# shieldrasp2.net
KiCad netlist of a schematic drawn in EAGLE
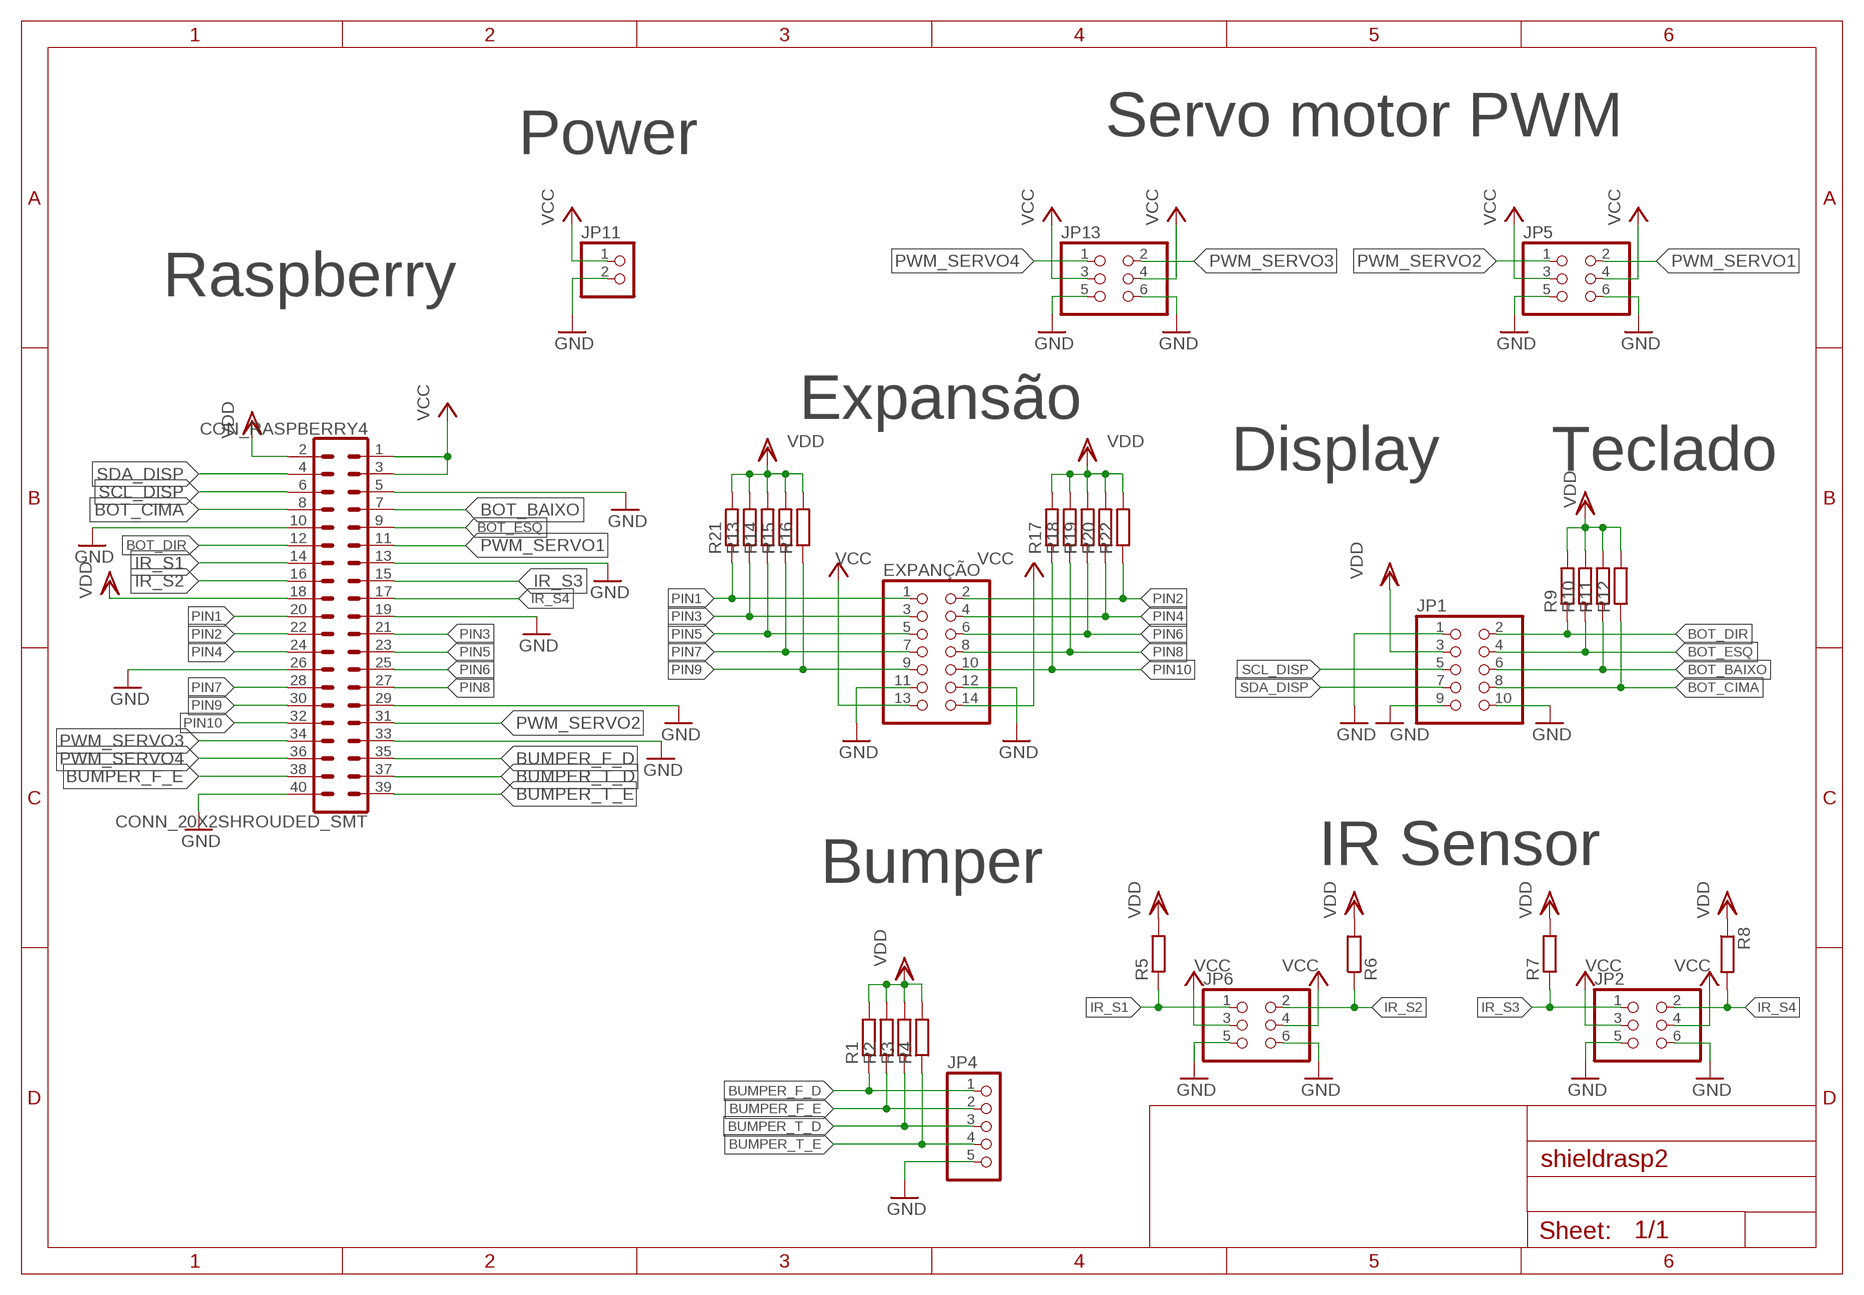
[diagram p0: schematic, sheet 1]

(export (version "E")
  (design (tool "Eeschema 10.0.6"))
  (components
    (comp (ref "CON_RASPBERRY4")
      (value "CONN_20X2SHROUDED_SMT")
      (footprint "eagle-import:2X20_SHROUDED_SMT")
      (libsource (lib "eagle-import") (part "CONN_20X2SHROUDED_SMT"))
    )
    (comp (ref "EXPANÇÃO")
      (value "PINHD-2X7")
      (footprint "eagle-import:2X07")
      (libsource (lib "eagle-import") (part "PINHD-2X7"))
    )
    (comp (ref "JP1")
      (value "PINHD-2X5/90")
      (footprint "eagle-import:2X05_90")
      (libsource (lib "eagle-import") (part "PINHD-2X5/90"))
    )
    (comp (ref "JP2")
      (value "PINHD-2X3/90")
      (footprint "eagle-import:2X03_90")
      (libsource (lib "eagle-import") (part "PINHD-2X3/90"))
    )
    (comp (ref "JP4")
      (value "PINHD-1X5/90")
      (footprint "eagle-import:1X05_90")
      (libsource (lib "eagle-import") (part "PINHD-1X5/90"))
    )
    (comp (ref "JP5")
      (value "PINHD-2X3/90")
      (footprint "eagle-import:2X03_90")
      (libsource (lib "eagle-import") (part "PINHD-2X3/90"))
    )
    (comp (ref "JP6")
      (value "PINHD-2X3/90")
      (footprint "eagle-import:2X03_90")
      (libsource (lib "eagle-import") (part "PINHD-2X3/90"))
    )
    (comp (ref "JP11")
      (value "PINHD-1X2/90")
      (footprint "eagle-import:1X02_90")
      (libsource (lib "eagle-import") (part "PINHD-1X2/90"))
    )
    (comp (ref "JP13")
      (value "PINHD-2X3/90")
      (footprint "eagle-import:2X03_90")
      (libsource (lib "eagle-import") (part "PINHD-2X3/90"))
    )
    (comp (ref "R1")
      (value "R-EU_M0805")
      (footprint "eagle-import:M0805")
      (libsource (lib "eagle-import") (part "R-EU_M0805"))
    )
    (comp (ref "R2")
      (value "R-EU_M0805")
      (footprint "eagle-import:M0805")
      (libsource (lib "eagle-import") (part "R-EU_M0805"))
    )
    (comp (ref "R3")
      (value "R-EU_M0805")
      (footprint "eagle-import:M0805")
      (libsource (lib "eagle-import") (part "R-EU_M0805"))
    )
    (comp (ref "R4")
      (value "R-EU_M0805")
      (footprint "eagle-import:M0805")
      (libsource (lib "eagle-import") (part "R-EU_M0805"))
    )
    (comp (ref "R5")
      (value "R-EU_M0805")
      (footprint "eagle-import:M0805")
      (libsource (lib "eagle-import") (part "R-EU_M0805"))
    )
    (comp (ref "R6")
      (value "R-EU_M0805")
      (footprint "eagle-import:M0805")
      (libsource (lib "eagle-import") (part "R-EU_M0805"))
    )
    (comp (ref "R7")
      (value "R-EU_M0805")
      (footprint "eagle-import:M0805")
      (libsource (lib "eagle-import") (part "R-EU_M0805"))
    )
    (comp (ref "R8")
      (value "R-EU_M0805")
      (footprint "eagle-import:M0805")
      (libsource (lib "eagle-import") (part "R-EU_M0805"))
    )
    (comp (ref "R9")
      (value "R-EU_M0805")
      (footprint "eagle-import:M0805")
      (libsource (lib "eagle-import") (part "R-EU_M0805"))
    )
    (comp (ref "R10")
      (value "R-EU_M0805")
      (footprint "eagle-import:M0805")
      (libsource (lib "eagle-import") (part "R-EU_M0805"))
    )
    (comp (ref "R11")
      (value "R-EU_M0805")
      (footprint "eagle-import:M0805")
      (libsource (lib "eagle-import") (part "R-EU_M0805"))
    )
    (comp (ref "R12")
      (value "R-EU_M0805")
      (footprint "eagle-import:M0805")
      (libsource (lib "eagle-import") (part "R-EU_M0805"))
    )
    (comp (ref "R13")
      (value "R-EU_M0805")
      (footprint "eagle-import:M0805")
      (libsource (lib "eagle-import") (part "R-EU_M0805"))
    )
    (comp (ref "R14")
      (value "R-EU_M0805")
      (footprint "eagle-import:M0805")
      (libsource (lib "eagle-import") (part "R-EU_M0805"))
    )
    (comp (ref "R15")
      (value "R-EU_M0805")
      (footprint "eagle-import:M0805")
      (libsource (lib "eagle-import") (part "R-EU_M0805"))
    )
    (comp (ref "R16")
      (value "R-EU_M0805")
      (footprint "eagle-import:M0805")
      (libsource (lib "eagle-import") (part "R-EU_M0805"))
    )
    (comp (ref "R17")
      (value "R-EU_M0805")
      (footprint "eagle-import:M0805")
      (libsource (lib "eagle-import") (part "R-EU_M0805"))
    )
    (comp (ref "R18")
      (value "R-EU_M0805")
      (footprint "eagle-import:M0805")
      (libsource (lib "eagle-import") (part "R-EU_M0805"))
    )
    (comp (ref "R19")
      (value "R-EU_M0805")
      (footprint "eagle-import:M0805")
      (libsource (lib "eagle-import") (part "R-EU_M0805"))
    )
    (comp (ref "R20")
      (value "R-EU_M0805")
      (footprint "eagle-import:M0805")
      (libsource (lib "eagle-import") (part "R-EU_M0805"))
    )
    (comp (ref "R21")
      (value "R-EU_M0805")
      (footprint "eagle-import:M0805")
      (libsource (lib "eagle-import") (part "R-EU_M0805"))
    )
    (comp (ref "R22")
      (value "R-EU_M0805")
      (footprint "eagle-import:M0805")
      (libsource (lib "eagle-import") (part "R-EU_M0805"))
    )
  )
  (nets
    (net (code "1") (name "BOT_BAIXO") (class "Default")
      (node (ref "CON_RASPBERRY4") (pin "7") (pinfunction "7_7") (pintype "passive"))
      (node (ref "JP1") (pin "6") (pinfunction "6_6") (pintype "passive"))
      (node (ref "R11") (pin "1") (pinfunction "1_1") (pintype "passive"))
    )
    (net (code "2") (name "BOT_CIMA") (class "Default")
      (node (ref "CON_RASPBERRY4") (pin "8") (pinfunction "8_8") (pintype "passive"))
      (node (ref "JP1") (pin "8") (pinfunction "8_8") (pintype "passive"))
      (node (ref "R12") (pin "1") (pinfunction "1_1") (pintype "passive"))
    )
    (net (code "3") (name "BOT_DIR") (class "Default")
      (node (ref "CON_RASPBERRY4") (pin "12") (pinfunction "12_12") (pintype "passive"))
      (node (ref "JP1") (pin "2") (pinfunction "2_2") (pintype "passive"))
      (node (ref "R9") (pin "1") (pinfunction "1_1") (pintype "passive"))
    )
    (net (code "4") (name "BOT_ESQ") (class "Default")
      (node (ref "CON_RASPBERRY4") (pin "9") (pinfunction "9_9") (pintype "passive"))
      (node (ref "JP1") (pin "4") (pinfunction "4_4") (pintype "passive"))
      (node (ref "R10") (pin "1") (pinfunction "1_1") (pintype "passive"))
    )
    (net (code "5") (name "BUMPER_F_D") (class "Default")
      (node (ref "CON_RASPBERRY4") (pin "35") (pinfunction "35_35") (pintype "passive"))
      (node (ref "JP4") (pin "1") (pinfunction "1_1") (pintype "passive"))
      (node (ref "R1") (pin "1") (pinfunction "1_1") (pintype "passive"))
    )
    (net (code "6") (name "BUMPER_F_E") (class "Default")
      (node (ref "CON_RASPBERRY4") (pin "38") (pinfunction "38_38") (pintype "passive"))
      (node (ref "JP4") (pin "2") (pinfunction "2_2") (pintype "passive"))
      (node (ref "R2") (pin "1") (pinfunction "1_1") (pintype "passive"))
    )
    (net (code "7") (name "BUMPER_T_D") (class "Default")
      (node (ref "CON_RASPBERRY4") (pin "37") (pinfunction "37_37") (pintype "passive"))
      (node (ref "JP4") (pin "3") (pinfunction "3_3") (pintype "passive"))
      (node (ref "R3") (pin "1") (pinfunction "1_1") (pintype "passive"))
    )
    (net (code "8") (name "BUMPER_T_E") (class "Default")
      (node (ref "CON_RASPBERRY4") (pin "39") (pinfunction "39_39") (pintype "passive"))
      (node (ref "JP4") (pin "4") (pinfunction "4_4") (pintype "passive"))
      (node (ref "R4") (pin "1") (pinfunction "1_1") (pintype "passive"))
    )
    (net (code "9") (name "GND") (class "Default")
      (node (ref "CON_RASPBERRY4") (pin "10") (pinfunction "10_10") (pintype "passive"))
      (node (ref "CON_RASPBERRY4") (pin "13") (pinfunction "13_13") (pintype "passive"))
      (node (ref "CON_RASPBERRY4") (pin "19") (pinfunction "19_19") (pintype "passive"))
      (node (ref "CON_RASPBERRY4") (pin "26") (pinfunction "26_26") (pintype "passive"))
      (node (ref "CON_RASPBERRY4") (pin "29") (pinfunction "29_29") (pintype "passive"))
      (node (ref "CON_RASPBERRY4") (pin "33") (pinfunction "33_33") (pintype "passive"))
      (node (ref "CON_RASPBERRY4") (pin "40") (pinfunction "40_40") (pintype "passive"))
      (node (ref "CON_RASPBERRY4") (pin "5") (pinfunction "5_5") (pintype "passive"))
      (node (ref "EXPANÇÃO") (pin "11") (pinfunction "11_11") (pintype "passive"))
      (node (ref "EXPANÇÃO") (pin "12") (pinfunction "12_12") (pintype "passive"))
      (node (ref "JP1") (pin "1") (pinfunction "1_1") (pintype "passive"))
      (node (ref "JP1") (pin "10") (pinfunction "10_10") (pintype "passive"))
      (node (ref "JP1") (pin "9") (pinfunction "9_9") (pintype "passive"))
      (node (ref "JP11") (pin "2") (pinfunction "2_2") (pintype "passive"))
      (node (ref "JP13") (pin "5") (pinfunction "5_5") (pintype "passive"))
      (node (ref "JP13") (pin "6") (pinfunction "6_6") (pintype "passive"))
      (node (ref "JP2") (pin "5") (pinfunction "5_5") (pintype "passive"))
      (node (ref "JP2") (pin "6") (pinfunction "6_6") (pintype "passive"))
      (node (ref "JP4") (pin "5") (pinfunction "5_5") (pintype "passive"))
      (node (ref "JP5") (pin "5") (pinfunction "5_5") (pintype "passive"))
      (node (ref "JP5") (pin "6") (pinfunction "6_6") (pintype "passive"))
      (node (ref "JP6") (pin "5") (pinfunction "5_5") (pintype "passive"))
      (node (ref "JP6") (pin "6") (pinfunction "6_6") (pintype "passive"))
    )
    (net (code "10") (name "IR_S1") (class "Default")
      (node (ref "CON_RASPBERRY4") (pin "14") (pinfunction "14_14") (pintype "passive"))
      (node (ref "JP6") (pin "1") (pinfunction "1_1") (pintype "passive"))
      (node (ref "R5") (pin "1") (pinfunction "1_1") (pintype "passive"))
    )
    (net (code "11") (name "IR_S2") (class "Default")
      (node (ref "CON_RASPBERRY4") (pin "16") (pinfunction "16_16") (pintype "passive"))
      (node (ref "JP6") (pin "2") (pinfunction "2_2") (pintype "passive"))
      (node (ref "R6") (pin "1") (pinfunction "1_1") (pintype "passive"))
    )
    (net (code "12") (name "IR_S3") (class "Default")
      (node (ref "CON_RASPBERRY4") (pin "15") (pinfunction "15_15") (pintype "passive"))
      (node (ref "JP2") (pin "1") (pinfunction "1_1") (pintype "passive"))
      (node (ref "R7") (pin "1") (pinfunction "1_1") (pintype "passive"))
    )
    (net (code "13") (name "IR_S4") (class "Default")
      (node (ref "CON_RASPBERRY4") (pin "17") (pinfunction "17_17") (pintype "passive"))
      (node (ref "JP2") (pin "2") (pinfunction "2_2") (pintype "passive"))
      (node (ref "R8") (pin "2") (pinfunction "2_2") (pintype "passive"))
    )
    (net (code "14") (name "PIN1") (class "Default")
      (node (ref "CON_RASPBERRY4") (pin "20") (pinfunction "20_20") (pintype "passive"))
      (node (ref "EXPANÇÃO") (pin "1") (pinfunction "1_1") (pintype "passive"))
      (node (ref "R21") (pin "1") (pinfunction "1_1") (pintype "passive"))
    )
    (net (code "15") (name "PIN2") (class "Default")
      (node (ref "CON_RASPBERRY4") (pin "22") (pinfunction "22_22") (pintype "passive"))
      (node (ref "EXPANÇÃO") (pin "2") (pinfunction "2_2") (pintype "passive"))
      (node (ref "R22") (pin "1") (pinfunction "1_1") (pintype "passive"))
    )
    (net (code "16") (name "PIN3") (class "Default")
      (node (ref "CON_RASPBERRY4") (pin "21") (pinfunction "21_21") (pintype "passive"))
      (node (ref "EXPANÇÃO") (pin "3") (pinfunction "3_3") (pintype "passive"))
      (node (ref "R13") (pin "1") (pinfunction "1_1") (pintype "passive"))
    )
    (net (code "17") (name "PIN4") (class "Default")
      (node (ref "CON_RASPBERRY4") (pin "24") (pinfunction "24_24") (pintype "passive"))
      (node (ref "EXPANÇÃO") (pin "4") (pinfunction "4_4") (pintype "passive"))
      (node (ref "R20") (pin "1") (pinfunction "1_1") (pintype "passive"))
    )
    (net (code "18") (name "PIN5") (class "Default")
      (node (ref "CON_RASPBERRY4") (pin "23") (pinfunction "23_23") (pintype "passive"))
      (node (ref "EXPANÇÃO") (pin "5") (pinfunction "5_5") (pintype "passive"))
      (node (ref "R14") (pin "1") (pinfunction "1_1") (pintype "passive"))
    )
    (net (code "19") (name "PIN6") (class "Default")
      (node (ref "CON_RASPBERRY4") (pin "25") (pinfunction "25_25") (pintype "passive"))
      (node (ref "EXPANÇÃO") (pin "6") (pinfunction "6_6") (pintype "passive"))
      (node (ref "R19") (pin "1") (pinfunction "1_1") (pintype "passive"))
    )
    (net (code "20") (name "PIN7") (class "Default")
      (node (ref "CON_RASPBERRY4") (pin "28") (pinfunction "28_28") (pintype "passive"))
      (node (ref "EXPANÇÃO") (pin "7") (pinfunction "7_7") (pintype "passive"))
      (node (ref "R15") (pin "1") (pinfunction "1_1") (pintype "passive"))
    )
    (net (code "21") (name "PIN8") (class "Default")
      (node (ref "CON_RASPBERRY4") (pin "27") (pinfunction "27_27") (pintype "passive"))
      (node (ref "EXPANÇÃO") (pin "8") (pinfunction "8_8") (pintype "passive"))
      (node (ref "R18") (pin "1") (pinfunction "1_1") (pintype "passive"))
    )
    (net (code "22") (name "PIN9") (class "Default")
      (node (ref "CON_RASPBERRY4") (pin "30") (pinfunction "30_30") (pintype "passive"))
      (node (ref "EXPANÇÃO") (pin "9") (pinfunction "9_9") (pintype "passive"))
      (node (ref "R16") (pin "1") (pinfunction "1_1") (pintype "passive"))
    )
    (net (code "23") (name "PIN10") (class "Default")
      (node (ref "CON_RASPBERRY4") (pin "32") (pinfunction "32_32") (pintype "passive"))
      (node (ref "EXPANÇÃO") (pin "10") (pinfunction "10_10") (pintype "passive"))
      (node (ref "R17") (pin "1") (pinfunction "1_1") (pintype "passive"))
    )
    (net (code "24") (name "PWM_SERVO1") (class "Default")
      (node (ref "CON_RASPBERRY4") (pin "11") (pinfunction "11_11") (pintype "passive"))
      (node (ref "JP5") (pin "2") (pinfunction "2_2") (pintype "passive"))
    )
    (net (code "25") (name "PWM_SERVO2") (class "Default")
      (node (ref "CON_RASPBERRY4") (pin "31") (pinfunction "31_31") (pintype "passive"))
      (node (ref "JP5") (pin "1") (pinfunction "1_1") (pintype "passive"))
    )
    (net (code "26") (name "PWM_SERVO3") (class "Default")
      (node (ref "CON_RASPBERRY4") (pin "34") (pinfunction "34_34") (pintype "passive"))
      (node (ref "JP13") (pin "2") (pinfunction "2_2") (pintype "passive"))
    )
    (net (code "27") (name "PWM_SERVO4") (class "Default")
      (node (ref "CON_RASPBERRY4") (pin "36") (pinfunction "36_36") (pintype "passive"))
      (node (ref "JP13") (pin "1") (pinfunction "1_1") (pintype "passive"))
    )
    (net (code "28") (name "SCL_DISP") (class "Default")
      (node (ref "CON_RASPBERRY4") (pin "6") (pinfunction "6_6") (pintype "passive"))
      (node (ref "JP1") (pin "5") (pinfunction "5_5") (pintype "passive"))
    )
    (net (code "29") (name "SDA_DISP") (class "Default")
      (node (ref "CON_RASPBERRY4") (pin "4") (pinfunction "4_4") (pintype "passive"))
      (node (ref "JP1") (pin "7") (pinfunction "7_7") (pintype "passive"))
    )
    (net (code "30") (name "VCC") (class "Default")
      (node (ref "CON_RASPBERRY4") (pin "1") (pinfunction "1_1") (pintype "passive"))
      (node (ref "CON_RASPBERRY4") (pin "3") (pinfunction "3_3") (pintype "passive"))
      (node (ref "EXPANÇÃO") (pin "13") (pinfunction "13_13") (pintype "passive"))
      (node (ref "EXPANÇÃO") (pin "14") (pinfunction "14_14") (pintype "passive"))
      (node (ref "JP11") (pin "1") (pinfunction "1_1") (pintype "passive"))
      (node (ref "JP13") (pin "3") (pinfunction "3_3") (pintype "passive"))
      (node (ref "JP13") (pin "4") (pinfunction "4_4") (pintype "passive"))
      (node (ref "JP2") (pin "3") (pinfunction "3_3") (pintype "passive"))
      (node (ref "JP2") (pin "4") (pinfunction "4_4") (pintype "passive"))
      (node (ref "JP5") (pin "3") (pinfunction "3_3") (pintype "passive"))
      (node (ref "JP5") (pin "4") (pinfunction "4_4") (pintype "passive"))
      (node (ref "JP6") (pin "3") (pinfunction "3_3") (pintype "passive"))
      (node (ref "JP6") (pin "4") (pinfunction "4_4") (pintype "passive"))
    )
    (net (code "31") (name "VDD") (class "Default")
      (node (ref "CON_RASPBERRY4") (pin "18") (pinfunction "18_18") (pintype "passive"))
      (node (ref "CON_RASPBERRY4") (pin "2") (pinfunction "2_2") (pintype "passive"))
      (node (ref "JP1") (pin "3") (pinfunction "3_3") (pintype "passive"))
      (node (ref "R1") (pin "2") (pinfunction "2_2") (pintype "passive"))
      (node (ref "R10") (pin "2") (pinfunction "2_2") (pintype "passive"))
      (node (ref "R11") (pin "2") (pinfunction "2_2") (pintype "passive"))
      (node (ref "R12") (pin "2") (pinfunction "2_2") (pintype "passive"))
      (node (ref "R13") (pin "2") (pinfunction "2_2") (pintype "passive"))
      (node (ref "R14") (pin "2") (pinfunction "2_2") (pintype "passive"))
      (node (ref "R15") (pin "2") (pinfunction "2_2") (pintype "passive"))
      (node (ref "R16") (pin "2") (pinfunction "2_2") (pintype "passive"))
      (node (ref "R17") (pin "2") (pinfunction "2_2") (pintype "passive"))
      (node (ref "R18") (pin "2") (pinfunction "2_2") (pintype "passive"))
      (node (ref "R19") (pin "2") (pinfunction "2_2") (pintype "passive"))
      (node (ref "R2") (pin "2") (pinfunction "2_2") (pintype "passive"))
      (node (ref "R20") (pin "2") (pinfunction "2_2") (pintype "passive"))
      (node (ref "R21") (pin "2") (pinfunction "2_2") (pintype "passive"))
      (node (ref "R22") (pin "2") (pinfunction "2_2") (pintype "passive"))
      (node (ref "R3") (pin "2") (pinfunction "2_2") (pintype "passive"))
      (node (ref "R4") (pin "2") (pinfunction "2_2") (pintype "passive"))
      (node (ref "R5") (pin "2") (pinfunction "2_2") (pintype "passive"))
      (node (ref "R6") (pin "2") (pinfunction "2_2") (pintype "passive"))
      (node (ref "R7") (pin "2") (pinfunction "2_2") (pintype "passive"))
      (node (ref "R8") (pin "1") (pinfunction "1_1") (pintype "passive"))
      (node (ref "R9") (pin "2") (pinfunction "2_2") (pintype "passive"))
    )
  )
)
